# LD1-001.net
KiCad netlist of a schematic drawn in EAGLE
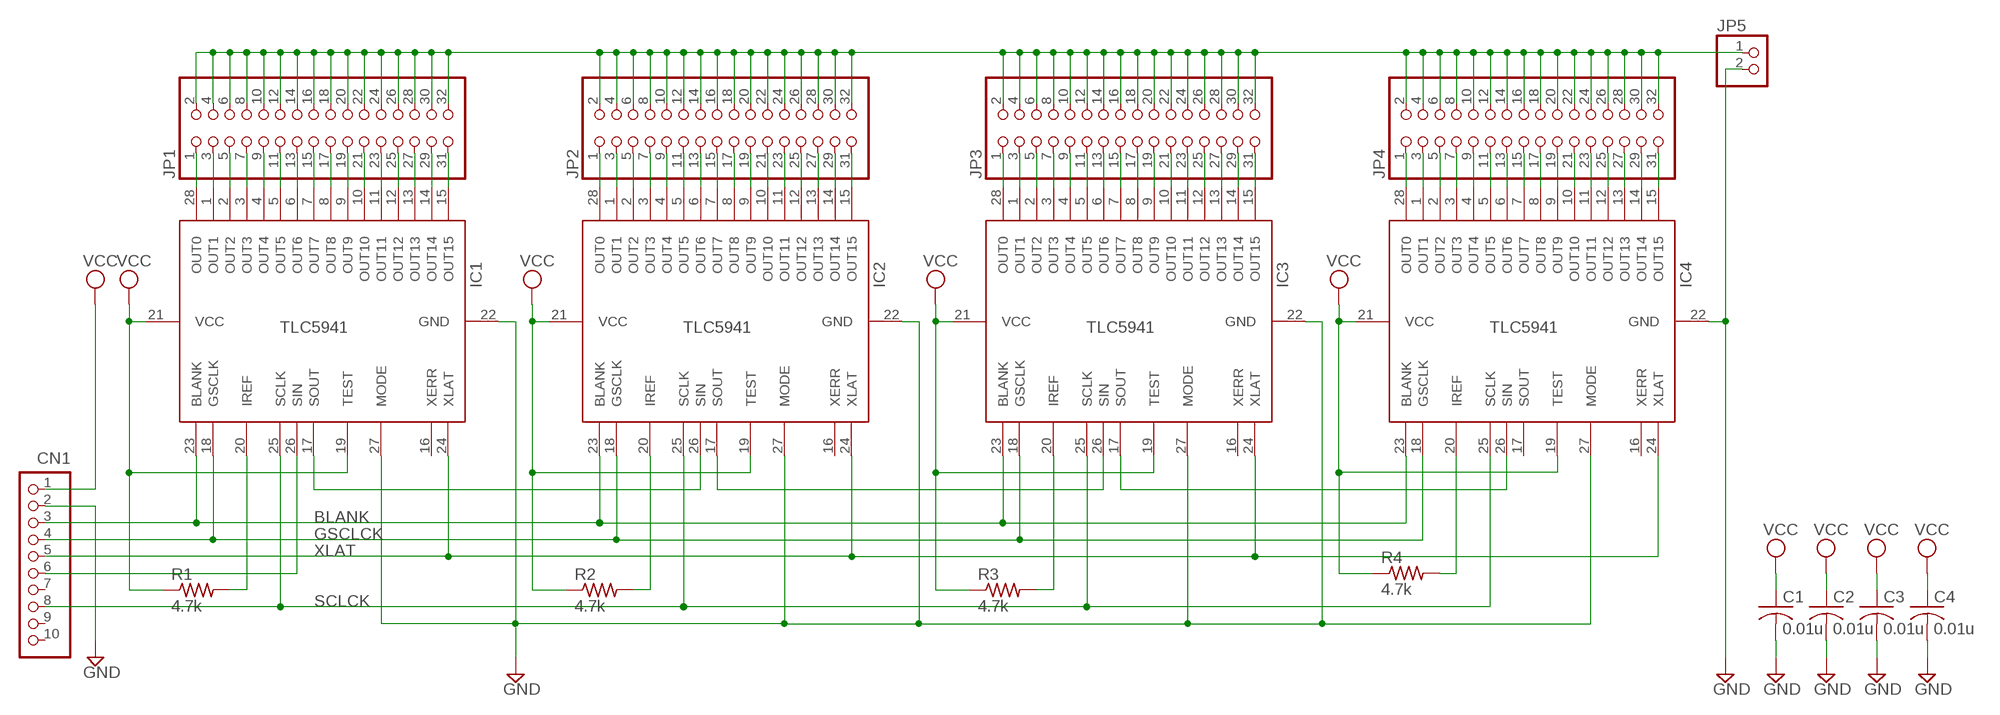
[diagram p0: schematic, sheet 1]

(export (version "E")
  (design (tool "Eeschema 10.0.6"))
  (components
    (comp (ref "C1")
      (value "0.01u")
      (footprint "eagle-import:C025-025X050")
      (libsource (lib "eagle-import") (part "C-US025-025X050"))
    )
    (comp (ref "C2")
      (value "0.01u")
      (footprint "eagle-import:C025-025X050")
      (libsource (lib "eagle-import") (part "C-US025-025X050"))
    )
    (comp (ref "C3")
      (value "0.01u")
      (footprint "eagle-import:C025-025X050")
      (libsource (lib "eagle-import") (part "C-US025-025X050"))
    )
    (comp (ref "C4")
      (value "0.01u")
      (footprint "eagle-import:C025-025X050")
      (libsource (lib "eagle-import") (part "C-US025-025X050"))
    )
    (comp (ref "CN1")
      (value "S10B-PH-K-S")
      (footprint "eagle-import:S10B-PH-K-S")
      (libsource (lib "eagle-import") (part "S10B-PH-K-S"))
    )
    (comp (ref "IC1")
      (value "TLC5941NT")
      (footprint "eagle-import:DIL28-3")
      (libsource (lib "eagle-import") (part "TLC5941NT"))
    )
    (comp (ref "IC2")
      (value "TLC5941NT")
      (footprint "eagle-import:DIL28-3")
      (libsource (lib "eagle-import") (part "TLC5941NT"))
    )
    (comp (ref "IC3")
      (value "TLC5941NT")
      (footprint "eagle-import:DIL28-3")
      (libsource (lib "eagle-import") (part "TLC5941NT"))
    )
    (comp (ref "IC4")
      (value "TLC5941NT")
      (footprint "eagle-import:DIL28-3")
      (libsource (lib "eagle-import") (part "TLC5941NT"))
    )
    (comp (ref "JP1")
      (value "PINHD-2X16")
      (footprint "eagle-import:2X16")
      (libsource (lib "eagle-import") (part "PINHD-2X16"))
    )
    (comp (ref "JP2")
      (value "PINHD-2X16")
      (footprint "eagle-import:2X16")
      (libsource (lib "eagle-import") (part "PINHD-2X16"))
    )
    (comp (ref "JP3")
      (value "PINHD-2X16")
      (footprint "eagle-import:2X16")
      (libsource (lib "eagle-import") (part "PINHD-2X16"))
    )
    (comp (ref "JP4")
      (value "PINHD-2X16")
      (footprint "eagle-import:2X16")
      (libsource (lib "eagle-import") (part "PINHD-2X16"))
    )
    (comp (ref "JP5")
      (value "PINHD-1X2")
      (footprint "eagle-import:1X02")
      (libsource (lib "eagle-import") (part "PINHD-1X2"))
    )
    (comp (ref "R1")
      (value "4.7k")
      (footprint "eagle-import:0204_5")
      (libsource (lib "eagle-import") (part "R-US_0204/5"))
    )
    (comp (ref "R2")
      (value "4.7k")
      (footprint "eagle-import:0204_5")
      (libsource (lib "eagle-import") (part "R-US_0204/5"))
    )
    (comp (ref "R3")
      (value "4.7k")
      (footprint "eagle-import:0204_5")
      (libsource (lib "eagle-import") (part "R-US_0204/5"))
    )
    (comp (ref "R4")
      (value "4.7k")
      (footprint "eagle-import:0204_5")
      (libsource (lib "eagle-import") (part "R-US_0204/5"))
    )
  )
  (nets
    (net (code "1") (name "/BLANK") (class "Default")
      (node (ref "CN1") (pin "3") (pinfunction "3_3") (pintype "passive"))
      (node (ref "IC1") (pin "23") (pinfunction "BLANK_23") (pintype "input"))
      (node (ref "IC2") (pin "23") (pinfunction "BLANK_23") (pintype "input"))
      (node (ref "IC3") (pin "23") (pinfunction "BLANK_23") (pintype "input"))
      (node (ref "IC4") (pin "23") (pinfunction "BLANK_23") (pintype "input"))
    )
    (net (code "2") (name "/GSCLCK") (class "Default")
      (node (ref "CN1") (pin "4") (pinfunction "4_4") (pintype "passive"))
      (node (ref "IC1") (pin "18") (pinfunction "GSCLK_18") (pintype "input"))
      (node (ref "IC2") (pin "18") (pinfunction "GSCLK_18") (pintype "input"))
      (node (ref "IC3") (pin "18") (pinfunction "GSCLK_18") (pintype "input"))
      (node (ref "IC4") (pin "18") (pinfunction "GSCLK_18") (pintype "input"))
    )
    (net (code "3") (name "/SCLCK") (class "Default")
      (node (ref "CN1") (pin "8") (pinfunction "8_8") (pintype "passive"))
      (node (ref "IC1") (pin "25") (pinfunction "SCLK_25") (pintype "input"))
      (node (ref "IC2") (pin "25") (pinfunction "SCLK_25") (pintype "input"))
      (node (ref "IC3") (pin "25") (pinfunction "SCLK_25") (pintype "input"))
      (node (ref "IC4") (pin "25") (pinfunction "SCLK_25") (pintype "input"))
    )
    (net (code "4") (name "/XLAT") (class "Default")
      (node (ref "CN1") (pin "5") (pinfunction "5_5") (pintype "passive"))
      (node (ref "IC1") (pin "24") (pinfunction "XLAT_24") (pintype "input"))
      (node (ref "IC2") (pin "24") (pinfunction "XLAT_24") (pintype "input"))
      (node (ref "IC3") (pin "24") (pinfunction "XLAT_24") (pintype "input"))
      (node (ref "IC4") (pin "24") (pinfunction "XLAT_24") (pintype "input"))
    )
    (net (code "5") (name "GND") (class "Default")
      (node (ref "C1") (pin "2") (pinfunction "2_2") (pintype "passive"))
      (node (ref "C2") (pin "2") (pinfunction "2_2") (pintype "passive"))
      (node (ref "C3") (pin "2") (pinfunction "2_2") (pintype "passive"))
      (node (ref "C4") (pin "2") (pinfunction "2_2") (pintype "passive"))
      (node (ref "CN1") (pin "2") (pinfunction "2_2") (pintype "passive"))
      (node (ref "IC1") (pin "22") (pinfunction "GND_22") (pintype "power_in"))
      (node (ref "IC1") (pin "27") (pinfunction "MODE_27") (pintype "input"))
      (node (ref "IC2") (pin "22") (pinfunction "GND_22") (pintype "power_in"))
      (node (ref "IC2") (pin "27") (pinfunction "MODE_27") (pintype "input"))
      (node (ref "IC3") (pin "22") (pinfunction "GND_22") (pintype "power_in"))
      (node (ref "IC3") (pin "27") (pinfunction "MODE_27") (pintype "input"))
      (node (ref "IC4") (pin "22") (pinfunction "GND_22") (pintype "power_in"))
      (node (ref "IC4") (pin "27") (pinfunction "MODE_27") (pintype "input"))
      (node (ref "JP5") (pin "2") (pinfunction "2_2") (pintype "passive"))
    )
    (net (code "6") (name "Net-(IC1-IREF)") (class "Default")
      (node (ref "IC1") (pin "20") (pinfunction "IREF_20") (pintype "bidirectional"))
      (node (ref "R1") (pin "2") (pinfunction "2_2") (pintype "passive"))
    )
    (net (code "7") (name "Net-(IC1-OUT0)") (class "Default")
      (node (ref "IC1") (pin "28") (pinfunction "OUT0_28") (pintype "output"))
      (node (ref "JP1") (pin "1") (pinfunction "1_1") (pintype "passive"))
    )
    (net (code "8") (name "Net-(IC1-OUT1)") (class "Default")
      (node (ref "IC1") (pin "1") (pinfunction "OUT1_1") (pintype "output"))
      (node (ref "JP1") (pin "3") (pinfunction "3_3") (pintype "passive"))
    )
    (net (code "9") (name "Net-(IC1-OUT2)") (class "Default")
      (node (ref "IC1") (pin "2") (pinfunction "OUT2_2") (pintype "output"))
      (node (ref "JP1") (pin "5") (pinfunction "5_5") (pintype "passive"))
    )
    (net (code "10") (name "Net-(IC1-OUT3)") (class "Default")
      (node (ref "IC1") (pin "3") (pinfunction "OUT3_3") (pintype "output"))
      (node (ref "JP1") (pin "7") (pinfunction "7_7") (pintype "passive"))
    )
    (net (code "11") (name "Net-(IC1-OUT4)") (class "Default")
      (node (ref "IC1") (pin "4") (pinfunction "OUT4_4") (pintype "output"))
      (node (ref "JP1") (pin "9") (pinfunction "9_9") (pintype "passive"))
    )
    (net (code "12") (name "Net-(IC1-OUT5)") (class "Default")
      (node (ref "IC1") (pin "5") (pinfunction "OUT5_5") (pintype "output"))
      (node (ref "JP1") (pin "11") (pinfunction "11_11") (pintype "passive"))
    )
    (net (code "13") (name "Net-(IC1-OUT6)") (class "Default")
      (node (ref "IC1") (pin "6") (pinfunction "OUT6_6") (pintype "output"))
      (node (ref "JP1") (pin "13") (pinfunction "13_13") (pintype "passive"))
    )
    (net (code "14") (name "Net-(IC1-OUT7)") (class "Default")
      (node (ref "IC1") (pin "7") (pinfunction "OUT7_7") (pintype "output"))
      (node (ref "JP1") (pin "15") (pinfunction "15_15") (pintype "passive"))
    )
    (net (code "15") (name "Net-(IC1-OUT8)") (class "Default")
      (node (ref "IC1") (pin "8") (pinfunction "OUT8_8") (pintype "output"))
      (node (ref "JP1") (pin "17") (pinfunction "17_17") (pintype "passive"))
    )
    (net (code "16") (name "Net-(IC1-OUT9)") (class "Default")
      (node (ref "IC1") (pin "9") (pinfunction "OUT9_9") (pintype "output"))
      (node (ref "JP1") (pin "19") (pinfunction "19_19") (pintype "passive"))
    )
    (net (code "17") (name "Net-(IC1-OUT10)") (class "Default")
      (node (ref "IC1") (pin "10") (pinfunction "OUT10_10") (pintype "output"))
      (node (ref "JP1") (pin "21") (pinfunction "21_21") (pintype "passive"))
    )
    (net (code "18") (name "Net-(IC1-OUT11)") (class "Default")
      (node (ref "IC1") (pin "11") (pinfunction "OUT11_11") (pintype "output"))
      (node (ref "JP1") (pin "23") (pinfunction "23_23") (pintype "passive"))
    )
    (net (code "19") (name "Net-(IC1-OUT12)") (class "Default")
      (node (ref "IC1") (pin "12") (pinfunction "OUT12_12") (pintype "output"))
      (node (ref "JP1") (pin "25") (pinfunction "25_25") (pintype "passive"))
    )
    (net (code "20") (name "Net-(IC1-OUT13)") (class "Default")
      (node (ref "IC1") (pin "13") (pinfunction "OUT13_13") (pintype "output"))
      (node (ref "JP1") (pin "27") (pinfunction "27_27") (pintype "passive"))
    )
    (net (code "21") (name "Net-(IC1-OUT14)") (class "Default")
      (node (ref "IC1") (pin "14") (pinfunction "OUT14_14") (pintype "output"))
      (node (ref "JP1") (pin "29") (pinfunction "29_29") (pintype "passive"))
    )
    (net (code "22") (name "Net-(IC1-OUT15)") (class "Default")
      (node (ref "IC1") (pin "15") (pinfunction "OUT15_15") (pintype "output"))
      (node (ref "JP1") (pin "31") (pinfunction "31_31") (pintype "passive"))
    )
    (net (code "23") (name "Net-(IC1-SIN)") (class "Default")
      (node (ref "CN1") (pin "6") (pinfunction "6_6") (pintype "passive"))
      (node (ref "IC1") (pin "26") (pinfunction "SIN_26") (pintype "input"))
    )
    (net (code "24") (name "Net-(IC1-SOUT)") (class "Default")
      (node (ref "IC1") (pin "17") (pinfunction "SOUT_17") (pintype "output"))
      (node (ref "IC2") (pin "26") (pinfunction "SIN_26") (pintype "input"))
    )
    (net (code "25") (name "Net-(IC2-IREF)") (class "Default")
      (node (ref "IC2") (pin "20") (pinfunction "IREF_20") (pintype "bidirectional"))
      (node (ref "R2") (pin "2") (pinfunction "2_2") (pintype "passive"))
    )
    (net (code "26") (name "Net-(IC2-OUT0)") (class "Default")
      (node (ref "IC2") (pin "28") (pinfunction "OUT0_28") (pintype "output"))
      (node (ref "JP2") (pin "1") (pinfunction "1_1") (pintype "passive"))
    )
    (net (code "27") (name "Net-(IC2-OUT1)") (class "Default")
      (node (ref "IC2") (pin "1") (pinfunction "OUT1_1") (pintype "output"))
      (node (ref "JP2") (pin "3") (pinfunction "3_3") (pintype "passive"))
    )
    (net (code "28") (name "Net-(IC2-OUT2)") (class "Default")
      (node (ref "IC2") (pin "2") (pinfunction "OUT2_2") (pintype "output"))
      (node (ref "JP2") (pin "5") (pinfunction "5_5") (pintype "passive"))
    )
    (net (code "29") (name "Net-(IC2-OUT3)") (class "Default")
      (node (ref "IC2") (pin "3") (pinfunction "OUT3_3") (pintype "output"))
      (node (ref "JP2") (pin "7") (pinfunction "7_7") (pintype "passive"))
    )
    (net (code "30") (name "Net-(IC2-OUT4)") (class "Default")
      (node (ref "IC2") (pin "4") (pinfunction "OUT4_4") (pintype "output"))
      (node (ref "JP2") (pin "9") (pinfunction "9_9") (pintype "passive"))
    )
    (net (code "31") (name "Net-(IC2-OUT5)") (class "Default")
      (node (ref "IC2") (pin "5") (pinfunction "OUT5_5") (pintype "output"))
      (node (ref "JP2") (pin "11") (pinfunction "11_11") (pintype "passive"))
    )
    (net (code "32") (name "Net-(IC2-OUT6)") (class "Default")
      (node (ref "IC2") (pin "6") (pinfunction "OUT6_6") (pintype "output"))
      (node (ref "JP2") (pin "13") (pinfunction "13_13") (pintype "passive"))
    )
    (net (code "33") (name "Net-(IC2-OUT7)") (class "Default")
      (node (ref "IC2") (pin "7") (pinfunction "OUT7_7") (pintype "output"))
      (node (ref "JP2") (pin "15") (pinfunction "15_15") (pintype "passive"))
    )
    (net (code "34") (name "Net-(IC2-OUT8)") (class "Default")
      (node (ref "IC2") (pin "8") (pinfunction "OUT8_8") (pintype "output"))
      (node (ref "JP2") (pin "17") (pinfunction "17_17") (pintype "passive"))
    )
    (net (code "35") (name "Net-(IC2-OUT9)") (class "Default")
      (node (ref "IC2") (pin "9") (pinfunction "OUT9_9") (pintype "output"))
      (node (ref "JP2") (pin "19") (pinfunction "19_19") (pintype "passive"))
    )
    (net (code "36") (name "Net-(IC2-OUT10)") (class "Default")
      (node (ref "IC2") (pin "10") (pinfunction "OUT10_10") (pintype "output"))
      (node (ref "JP2") (pin "21") (pinfunction "21_21") (pintype "passive"))
    )
    (net (code "37") (name "Net-(IC2-OUT11)") (class "Default")
      (node (ref "IC2") (pin "11") (pinfunction "OUT11_11") (pintype "output"))
      (node (ref "JP2") (pin "23") (pinfunction "23_23") (pintype "passive"))
    )
    (net (code "38") (name "Net-(IC2-OUT12)") (class "Default")
      (node (ref "IC2") (pin "12") (pinfunction "OUT12_12") (pintype "output"))
      (node (ref "JP2") (pin "25") (pinfunction "25_25") (pintype "passive"))
    )
    (net (code "39") (name "Net-(IC2-OUT13)") (class "Default")
      (node (ref "IC2") (pin "13") (pinfunction "OUT13_13") (pintype "output"))
      (node (ref "JP2") (pin "27") (pinfunction "27_27") (pintype "passive"))
    )
    (net (code "40") (name "Net-(IC2-OUT14)") (class "Default")
      (node (ref "IC2") (pin "14") (pinfunction "OUT14_14") (pintype "output"))
      (node (ref "JP2") (pin "29") (pinfunction "29_29") (pintype "passive"))
    )
    (net (code "41") (name "Net-(IC2-OUT15)") (class "Default")
      (node (ref "IC2") (pin "15") (pinfunction "OUT15_15") (pintype "output"))
      (node (ref "JP2") (pin "31") (pinfunction "31_31") (pintype "passive"))
    )
    (net (code "42") (name "Net-(IC2-SOUT)") (class "Default")
      (node (ref "IC2") (pin "17") (pinfunction "SOUT_17") (pintype "output"))
      (node (ref "IC3") (pin "26") (pinfunction "SIN_26") (pintype "input"))
    )
    (net (code "43") (name "Net-(IC3-IREF)") (class "Default")
      (node (ref "IC3") (pin "20") (pinfunction "IREF_20") (pintype "bidirectional"))
      (node (ref "R3") (pin "2") (pinfunction "2_2") (pintype "passive"))
    )
    (net (code "44") (name "Net-(IC3-OUT0)") (class "Default")
      (node (ref "IC3") (pin "28") (pinfunction "OUT0_28") (pintype "output"))
      (node (ref "JP3") (pin "1") (pinfunction "1_1") (pintype "passive"))
    )
    (net (code "45") (name "Net-(IC3-OUT1)") (class "Default")
      (node (ref "IC3") (pin "1") (pinfunction "OUT1_1") (pintype "output"))
      (node (ref "JP3") (pin "3") (pinfunction "3_3") (pintype "passive"))
    )
    (net (code "46") (name "Net-(IC3-OUT2)") (class "Default")
      (node (ref "IC3") (pin "2") (pinfunction "OUT2_2") (pintype "output"))
      (node (ref "JP3") (pin "5") (pinfunction "5_5") (pintype "passive"))
    )
    (net (code "47") (name "Net-(IC3-OUT3)") (class "Default")
      (node (ref "IC3") (pin "3") (pinfunction "OUT3_3") (pintype "output"))
      (node (ref "JP3") (pin "7") (pinfunction "7_7") (pintype "passive"))
    )
    (net (code "48") (name "Net-(IC3-OUT4)") (class "Default")
      (node (ref "IC3") (pin "4") (pinfunction "OUT4_4") (pintype "output"))
      (node (ref "JP3") (pin "9") (pinfunction "9_9") (pintype "passive"))
    )
    (net (code "49") (name "Net-(IC3-OUT5)") (class "Default")
      (node (ref "IC3") (pin "5") (pinfunction "OUT5_5") (pintype "output"))
      (node (ref "JP3") (pin "11") (pinfunction "11_11") (pintype "passive"))
    )
    (net (code "50") (name "Net-(IC3-OUT6)") (class "Default")
      (node (ref "IC3") (pin "6") (pinfunction "OUT6_6") (pintype "output"))
      (node (ref "JP3") (pin "13") (pinfunction "13_13") (pintype "passive"))
    )
    (net (code "51") (name "Net-(IC3-OUT7)") (class "Default")
      (node (ref "IC3") (pin "7") (pinfunction "OUT7_7") (pintype "output"))
      (node (ref "JP3") (pin "15") (pinfunction "15_15") (pintype "passive"))
    )
    (net (code "52") (name "Net-(IC3-OUT8)") (class "Default")
      (node (ref "IC3") (pin "8") (pinfunction "OUT8_8") (pintype "output"))
      (node (ref "JP3") (pin "17") (pinfunction "17_17") (pintype "passive"))
    )
    (net (code "53") (name "Net-(IC3-OUT9)") (class "Default")
      (node (ref "IC3") (pin "9") (pinfunction "OUT9_9") (pintype "output"))
      (node (ref "JP3") (pin "19") (pinfunction "19_19") (pintype "passive"))
    )
    (net (code "54") (name "Net-(IC3-OUT10)") (class "Default")
      (node (ref "IC3") (pin "10") (pinfunction "OUT10_10") (pintype "output"))
      (node (ref "JP3") (pin "21") (pinfunction "21_21") (pintype "passive"))
    )
    (net (code "55") (name "Net-(IC3-OUT11)") (class "Default")
      (node (ref "IC3") (pin "11") (pinfunction "OUT11_11") (pintype "output"))
      (node (ref "JP3") (pin "23") (pinfunction "23_23") (pintype "passive"))
    )
    (net (code "56") (name "Net-(IC3-OUT12)") (class "Default")
      (node (ref "IC3") (pin "12") (pinfunction "OUT12_12") (pintype "output"))
      (node (ref "JP3") (pin "25") (pinfunction "25_25") (pintype "passive"))
    )
    (net (code "57") (name "Net-(IC3-OUT13)") (class "Default")
      (node (ref "IC3") (pin "13") (pinfunction "OUT13_13") (pintype "output"))
      (node (ref "JP3") (pin "27") (pinfunction "27_27") (pintype "passive"))
    )
    (net (code "58") (name "Net-(IC3-OUT14)") (class "Default")
      (node (ref "IC3") (pin "14") (pinfunction "OUT14_14") (pintype "output"))
      (node (ref "JP3") (pin "29") (pinfunction "29_29") (pintype "passive"))
    )
    (net (code "59") (name "Net-(IC3-OUT15)") (class "Default")
      (node (ref "IC3") (pin "15") (pinfunction "OUT15_15") (pintype "output"))
      (node (ref "JP3") (pin "31") (pinfunction "31_31") (pintype "passive"))
    )
    (net (code "60") (name "Net-(IC3-SOUT)") (class "Default")
      (node (ref "IC3") (pin "17") (pinfunction "SOUT_17") (pintype "output"))
      (node (ref "IC4") (pin "26") (pinfunction "SIN_26") (pintype "input"))
    )
    (net (code "61") (name "Net-(IC4-IREF)") (class "Default")
      (node (ref "IC4") (pin "20") (pinfunction "IREF_20") (pintype "bidirectional"))
      (node (ref "R4") (pin "2") (pinfunction "2_2") (pintype "passive"))
    )
    (net (code "62") (name "Net-(IC4-OUT0)") (class "Default")
      (node (ref "IC4") (pin "28") (pinfunction "OUT0_28") (pintype "output"))
      (node (ref "JP4") (pin "1") (pinfunction "1_1") (pintype "passive"))
    )
    (net (code "63") (name "Net-(IC4-OUT1)") (class "Default")
      (node (ref "IC4") (pin "1") (pinfunction "OUT1_1") (pintype "output"))
      (node (ref "JP4") (pin "3") (pinfunction "3_3") (pintype "passive"))
    )
    (net (code "64") (name "Net-(IC4-OUT2)") (class "Default")
      (node (ref "IC4") (pin "2") (pinfunction "OUT2_2") (pintype "output"))
      (node (ref "JP4") (pin "5") (pinfunction "5_5") (pintype "passive"))
    )
    (net (code "65") (name "Net-(IC4-OUT3)") (class "Default")
      (node (ref "IC4") (pin "3") (pinfunction "OUT3_3") (pintype "output"))
      (node (ref "JP4") (pin "7") (pinfunction "7_7") (pintype "passive"))
    )
    (net (code "66") (name "Net-(IC4-OUT4)") (class "Default")
      (node (ref "IC4") (pin "4") (pinfunction "OUT4_4") (pintype "output"))
      (node (ref "JP4") (pin "9") (pinfunction "9_9") (pintype "passive"))
    )
    (net (code "67") (name "Net-(IC4-OUT5)") (class "Default")
      (node (ref "IC4") (pin "5") (pinfunction "OUT5_5") (pintype "output"))
      (node (ref "JP4") (pin "11") (pinfunction "11_11") (pintype "passive"))
    )
    (net (code "68") (name "Net-(IC4-OUT6)") (class "Default")
      (node (ref "IC4") (pin "6") (pinfunction "OUT6_6") (pintype "output"))
      (node (ref "JP4") (pin "13") (pinfunction "13_13") (pintype "passive"))
    )
    (net (code "69") (name "Net-(IC4-OUT7)") (class "Default")
      (node (ref "IC4") (pin "7") (pinfunction "OUT7_7") (pintype "output"))
      (node (ref "JP4") (pin "15") (pinfunction "15_15") (pintype "passive"))
    )
    (net (code "70") (name "Net-(IC4-OUT8)") (class "Default")
      (node (ref "IC4") (pin "8") (pinfunction "OUT8_8") (pintype "output"))
      (node (ref "JP4") (pin "17") (pinfunction "17_17") (pintype "passive"))
    )
    (net (code "71") (name "Net-(IC4-OUT9)") (class "Default")
      (node (ref "IC4") (pin "9") (pinfunction "OUT9_9") (pintype "output"))
      (node (ref "JP4") (pin "19") (pinfunction "19_19") (pintype "passive"))
    )
    (net (code "72") (name "Net-(IC4-OUT10)") (class "Default")
      (node (ref "IC4") (pin "10") (pinfunction "OUT10_10") (pintype "output"))
      (node (ref "JP4") (pin "21") (pinfunction "21_21") (pintype "passive"))
    )
    (net (code "73") (name "Net-(IC4-OUT11)") (class "Default")
      (node (ref "IC4") (pin "11") (pinfunction "OUT11_11") (pintype "output"))
      (node (ref "JP4") (pin "23") (pinfunction "23_23") (pintype "passive"))
    )
    (net (code "74") (name "Net-(IC4-OUT12)") (class "Default")
      (node (ref "IC4") (pin "12") (pinfunction "OUT12_12") (pintype "output"))
      (node (ref "JP4") (pin "25") (pinfunction "25_25") (pintype "passive"))
    )
    (net (code "75") (name "Net-(IC4-OUT13)") (class "Default")
      (node (ref "IC4") (pin "13") (pinfunction "OUT13_13") (pintype "output"))
      (node (ref "JP4") (pin "27") (pinfunction "27_27") (pintype "passive"))
    )
    (net (code "76") (name "Net-(IC4-OUT14)") (class "Default")
      (node (ref "IC4") (pin "14") (pinfunction "OUT14_14") (pintype "output"))
      (node (ref "JP4") (pin "29") (pinfunction "29_29") (pintype "passive"))
    )
    (net (code "77") (name "Net-(IC4-OUT15)") (class "Default")
      (node (ref "IC4") (pin "15") (pinfunction "OUT15_15") (pintype "output"))
      (node (ref "JP4") (pin "31") (pinfunction "31_31") (pintype "passive"))
    )
    (net (code "78") (name "Net-(JP1-Pad10)") (class "Default")
      (node (ref "JP1") (pin "10") (pinfunction "10_10") (pintype "passive"))
      (node (ref "JP1") (pin "12") (pinfunction "12_12") (pintype "passive"))
      (node (ref "JP1") (pin "14") (pinfunction "14_14") (pintype "passive"))
      (node (ref "JP1") (pin "16") (pinfunction "16_16") (pintype "passive"))
      (node (ref "JP1") (pin "18") (pinfunction "18_18") (pintype "passive"))
      (node (ref "JP1") (pin "2") (pinfunction "2_2") (pintype "passive"))
      (node (ref "JP1") (pin "20") (pinfunction "20_20") (pintype "passive"))
      (node (ref "JP1") (pin "22") (pinfunction "22_22") (pintype "passive"))
      (node (ref "JP1") (pin "24") (pinfunction "24_24") (pintype "passive"))
      (node (ref "JP1") (pin "26") (pinfunction "26_26") (pintype "passive"))
      (node (ref "JP1") (pin "28") (pinfunction "28_28") (pintype "passive"))
      (node (ref "JP1") (pin "30") (pinfunction "30_30") (pintype "passive"))
      (node (ref "JP1") (pin "32") (pinfunction "32_32") (pintype "passive"))
      (node (ref "JP1") (pin "4") (pinfunction "4_4") (pintype "passive"))
      (node (ref "JP1") (pin "6") (pinfunction "6_6") (pintype "passive"))
      (node (ref "JP1") (pin "8") (pinfunction "8_8") (pintype "passive"))
      (node (ref "JP2") (pin "10") (pinfunction "10_10") (pintype "passive"))
      (node (ref "JP2") (pin "12") (pinfunction "12_12") (pintype "passive"))
      (node (ref "JP2") (pin "14") (pinfunction "14_14") (pintype "passive"))
      (node (ref "JP2") (pin "16") (pinfunction "16_16") (pintype "passive"))
      (node (ref "JP2") (pin "18") (pinfunction "18_18") (pintype "passive"))
      (node (ref "JP2") (pin "2") (pinfunction "2_2") (pintype "passive"))
      (node (ref "JP2") (pin "20") (pinfunction "20_20") (pintype "passive"))
      (node (ref "JP2") (pin "22") (pinfunction "22_22") (pintype "passive"))
      (node (ref "JP2") (pin "24") (pinfunction "24_24") (pintype "passive"))
      (node (ref "JP2") (pin "26") (pinfunction "26_26") (pintype "passive"))
      (node (ref "JP2") (pin "28") (pinfunction "28_28") (pintype "passive"))
      (node (ref "JP2") (pin "30") (pinfunction "30_30") (pintype "passive"))
      (node (ref "JP2") (pin "32") (pinfunction "32_32") (pintype "passive"))
      (node (ref "JP2") (pin "4") (pinfunction "4_4") (pintype "passive"))
      (node (ref "JP2") (pin "6") (pinfunction "6_6") (pintype "passive"))
      (node (ref "JP2") (pin "8") (pinfunction "8_8") (pintype "passive"))
      (node (ref "JP3") (pin "10") (pinfunction "10_10") (pintype "passive"))
      (node (ref "JP3") (pin "12") (pinfunction "12_12") (pintype "passive"))
      (node (ref "JP3") (pin "14") (pinfunction "14_14") (pintype "passive"))
      (node (ref "JP3") (pin "16") (pinfunction "16_16") (pintype "passive"))
      (node (ref "JP3") (pin "18") (pinfunction "18_18") (pintype "passive"))
      (node (ref "JP3") (pin "2") (pinfunction "2_2") (pintype "passive"))
      (node (ref "JP3") (pin "20") (pinfunction "20_20") (pintype "passive"))
      (node (ref "JP3") (pin "22") (pinfunction "22_22") (pintype "passive"))
      (node (ref "JP3") (pin "24") (pinfunction "24_24") (pintype "passive"))
      (node (ref "JP3") (pin "26") (pinfunction "26_26") (pintype "passive"))
      (node (ref "JP3") (pin "28") (pinfunction "28_28") (pintype "passive"))
      (node (ref "JP3") (pin "30") (pinfunction "30_30") (pintype "passive"))
      (node (ref "JP3") (pin "32") (pinfunction "32_32") (pintype "passive"))
      (node (ref "JP3") (pin "4") (pinfunction "4_4") (pintype "passive"))
      (node (ref "JP3") (pin "6") (pinfunction "6_6") (pintype "passive"))
      (node (ref "JP3") (pin "8") (pinfunction "8_8") (pintype "passive"))
      (node (ref "JP4") (pin "10") (pinfunction "10_10") (pintype "passive"))
      (node (ref "JP4") (pin "12") (pinfunction "12_12") (pintype "passive"))
      (node (ref "JP4") (pin "14") (pinfunction "14_14") (pintype "passive"))
      (node (ref "JP4") (pin "16") (pinfunction "16_16") (pintype "passive"))
      (node (ref "JP4") (pin "18") (pinfunction "18_18") (pintype "passive"))
      (node (ref "JP4") (pin "2") (pinfunction "2_2") (pintype "passive"))
      (node (ref "JP4") (pin "20") (pinfunction "20_20") (pintype "passive"))
      (node (ref "JP4") (pin "22") (pinfunction "22_22") (pintype "passive"))
      (node (ref "JP4") (pin "24") (pinfunction "24_24") (pintype "passive"))
      (node (ref "JP4") (pin "26") (pinfunction "26_26") (pintype "passive"))
      (node (ref "JP4") (pin "28") (pinfunction "28_28") (pintype "passive"))
      (node (ref "JP4") (pin "30") (pinfunction "30_30") (pintype "passive"))
      (node (ref "JP4") (pin "32") (pinfunction "32_32") (pintype "passive"))
      (node (ref "JP4") (pin "4") (pinfunction "4_4") (pintype "passive"))
      (node (ref "JP4") (pin "6") (pinfunction "6_6") (pintype "passive"))
      (node (ref "JP4") (pin "8") (pinfunction "8_8") (pintype "passive"))
      (node (ref "JP5") (pin "1") (pinfunction "1_1") (pintype "passive"))
    )
    (net (code "79") (name "VCC") (class "Default")
      (node (ref "C1") (pin "1") (pinfunction "1_1") (pintype "passive"))
      (node (ref "C2") (pin "1") (pinfunction "1_1") (pintype "passive"))
      (node (ref "C3") (pin "1") (pinfunction "1_1") (pintype "passive"))
      (node (ref "C4") (pin "1") (pinfunction "1_1") (pintype "passive"))
      (node (ref "CN1") (pin "1") (pinfunction "1_1") (pintype "passive"))
      (node (ref "IC1") (pin "19") (pinfunction "TEST_19") (pintype "input"))
      (node (ref "IC1") (pin "21") (pinfunction "VCC_21") (pintype "power_in"))
      (node (ref "IC2") (pin "19") (pinfunction "TEST_19") (pintype "input"))
      (node (ref "IC2") (pin "21") (pinfunction "VCC_21") (pintype "power_in"))
      (node (ref "IC3") (pin "19") (pinfunction "TEST_19") (pintype "input"))
      (node (ref "IC3") (pin "21") (pinfunction "VCC_21") (pintype "power_in"))
      (node (ref "IC4") (pin "19") (pinfunction "TEST_19") (pintype "input"))
      (node (ref "IC4") (pin "21") (pinfunction "VCC_21") (pintype "power_in"))
      (node (ref "R1") (pin "1") (pinfunction "1_1") (pintype "passive"))
      (node (ref "R2") (pin "1") (pinfunction "1_1") (pintype "passive"))
      (node (ref "R3") (pin "1") (pinfunction "1_1") (pintype "passive"))
      (node (ref "R4") (pin "1") (pinfunction "1_1") (pintype "passive"))
    )
    (net (code "80") (name "unconnected-(CN1-Pad7)") (class "Default")
      (node (ref "CN1") (pin "7") (pinfunction "7_7") (pintype "passive"))
    )
    (net (code "81") (name "unconnected-(CN1-Pad9)") (class "Default")
      (node (ref "CN1") (pin "9") (pinfunction "9_9") (pintype "passive"))
    )
    (net (code "82") (name "unconnected-(CN1-Pad10)") (class "Default")
      (node (ref "CN1") (pin "10") (pinfunction "10_10") (pintype "passive"))
    )
    (net (code "83") (name "unconnected-(IC1-XERR-Pad16)") (class "Default")
      (node (ref "IC1") (pin "16") (pinfunction "XERR_16") (pintype "output"))
    )
    (net (code "84") (name "unconnected-(IC2-XERR-Pad16)") (class "Default")
      (node (ref "IC2") (pin "16") (pinfunction "XERR_16") (pintype "output"))
    )
    (net (code "85") (name "unconnected-(IC3-XERR-Pad16)") (class "Default")
      (node (ref "IC3") (pin "16") (pinfunction "XERR_16") (pintype "output"))
    )
    (net (code "86") (name "unconnected-(IC4-SOUT-Pad17)") (class "Default")
      (node (ref "IC4") (pin "17") (pinfunction "SOUT_17") (pintype "output"))
    )
    (net (code "87") (name "unconnected-(IC4-XERR-Pad16)") (class "Default")
      (node (ref "IC4") (pin "16") (pinfunction "XERR_16") (pintype "output"))
    )
  )
)
